# Mach1.net
KiCad netlist of a schematic drawn in Altium Designer
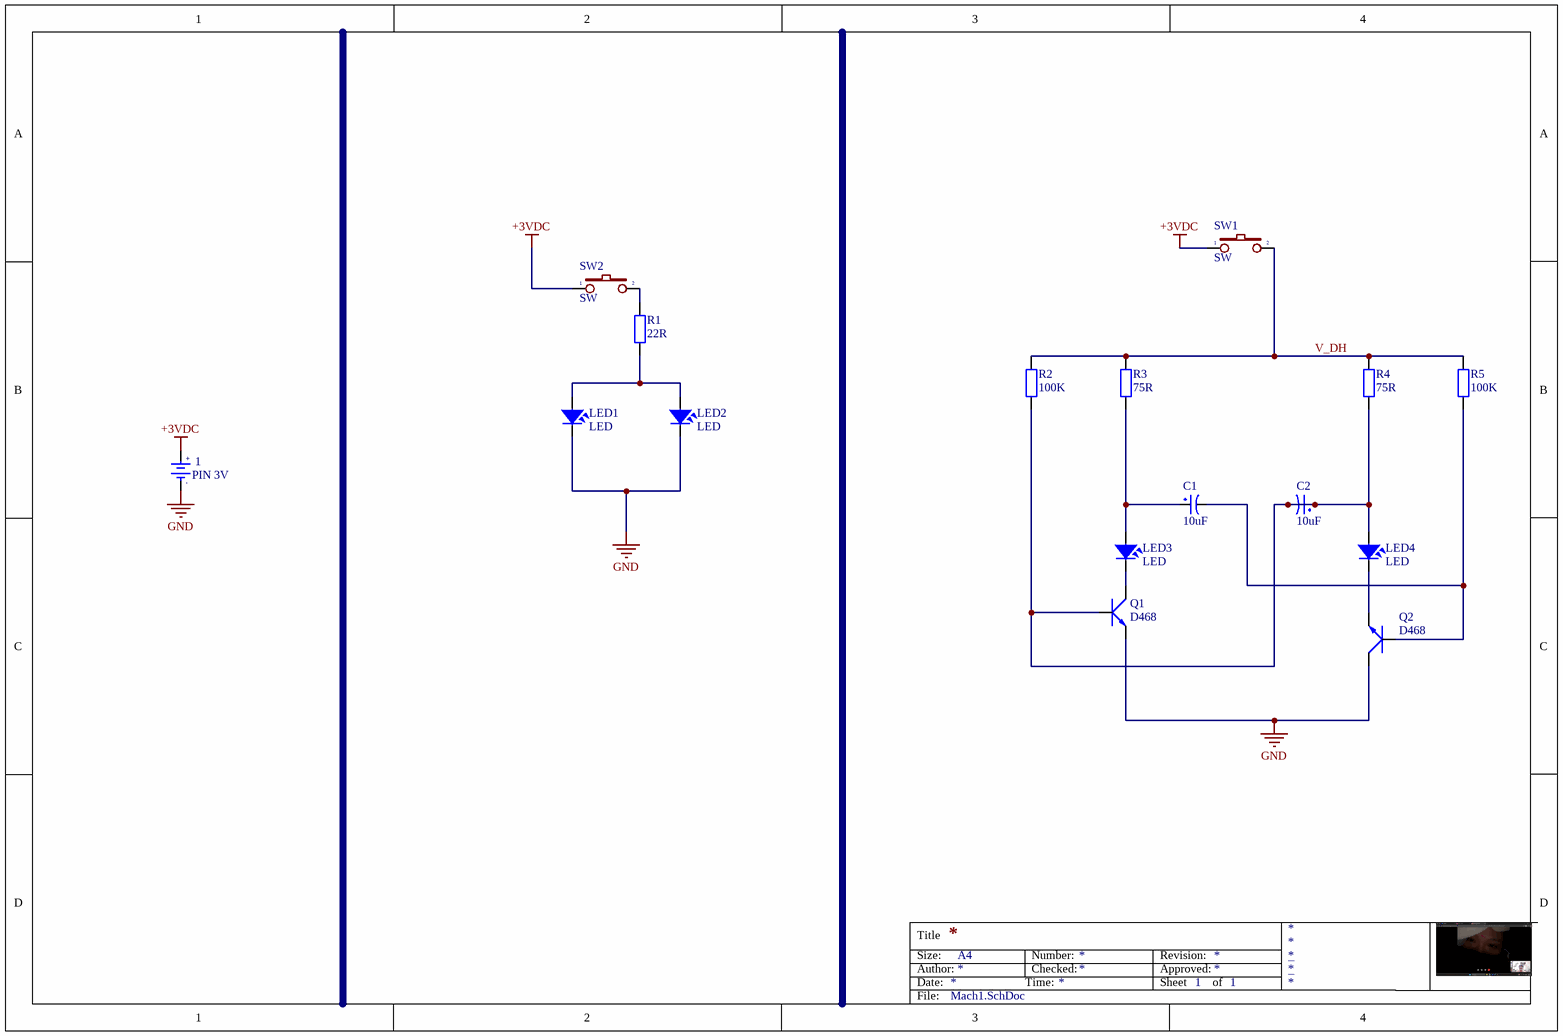
[diagram p0: Mach1.SchDoc]

(export (version "E")
  (design (tool "Eeschema 10.0.6"))
  (components
    (comp (ref "1")
      (value "PIN 3V")
      (footprint "PIN3V")
      (description "Battery 3VDC")
      (libsource (lib "KhanhBK_SCH_Library_2") (part "PIN 3V"))
    )
    (comp (ref "C1")
      (value "10uF")
      (footprint "CP1/2")
      (description "Cap P  0,1uF < 22uF , 16 - 50V")
      (libsource (lib "KhanhBK_SCH_Library_2") (part "CP1"))
    )
    (comp (ref "C2")
      (value "10uF")
      (footprint "CP1/2")
      (description "Cap P  0,1uF < 22uF , 16 - 50V")
      (libsource (lib "KhanhBK_SCH_Library_2") (part "CP1"))
    )
    (comp (ref "LED1")
      (value "LED")
      (footprint "LED-5 GRe")
      (description "LED Single colour Green and Red")
      (libsource (lib "KhanhBK_SCH_Library_2") (part "LED"))
    )
    (comp (ref "LED2")
      (value "LED")
      (footprint "LED-5 GRe")
      (description "LED Single colour Green and Red")
      (libsource (lib "KhanhBK_SCH_Library_2") (part "LED"))
    )
    (comp (ref "LED3")
      (value "LED")
      (footprint "LED-5 GRe")
      (description "LED Single colour Green and Red")
      (libsource (lib "KhanhBK_SCH_Library_2") (part "LED"))
    )
    (comp (ref "LED4")
      (value "LED")
      (footprint "LED-5TRED")
      (description "LED Single colour Green and Red")
      (libsource (lib "KhanhBK_SCH_Library_2") (part "LED"))
    )
    (comp (ref "Q1")
      (value "D468")
      (footprint "QTO-92")
      (description "P 600mW, ECB")
      (libsource (lib "KhanhBK_SCH_Library_2") (part "NPN_ECB"))
    )
    (comp (ref "Q2")
      (value "D468")
      (footprint "QTO-92")
      (description "P 600mW, ECB")
      (libsource (lib "KhanhBK_SCH_Library_2") (part "NPN_ECB"))
    )
    (comp (ref "R1")
      (value "22R")
      (footprint "RES-1/4W-SMALL")
      (description "Resistor 1/4W")
      (libsource (lib "KhanhBK_SCH_Library_2") (part "RES 1/4W"))
    )
    (comp (ref "R2")
      (value "100K")
      (footprint "RES-1/4W-SMALL")
      (description "Resistor 1/4W")
      (libsource (lib "KhanhBK_SCH_Library_2") (part "RES 1/4W"))
    )
    (comp (ref "R3")
      (value "75R")
      (footprint "RES-1/4W-SMALL")
      (description "Resistor 1/4W")
      (libsource (lib "KhanhBK_SCH_Library_2") (part "RES 1/4W"))
    )
    (comp (ref "R4")
      (value "75R")
      (footprint "RES-1/4W-SMALL")
      (description "Resistor 1/4W")
      (libsource (lib "KhanhBK_SCH_Library_2") (part "RES 1/4W"))
    )
    (comp (ref "R5")
      (value "100K")
      (footprint "RES-1/4W-SMALL")
      (description "Resistor 1/4W")
      (libsource (lib "KhanhBK_SCH_Library_2") (part "RES 1/4W"))
    )
    (comp (ref "SW1")
      (value "SW")
      (footprint "SW2")
      (description "Switch button 2 pin")
      (libsource (lib "KhanhBK_SCH_Library_2") (part "SW2"))
    )
    (comp (ref "SW2")
      (value "SW")
      (footprint "SW2")
      (description "Switch button 2 pin")
      (libsource (lib "KhanhBK_SCH_Library_2") (part "SW2"))
    )
  )
  (nets
    (net (code "1") (name "+3VDC") (class "Default")
      (node (ref "1") (pin "1") (pinfunction "+3V_1") (pintype "passive"))
      (node (ref "SW1") (pin "1") (pinfunction "1_1") (pintype "passive"))
      (node (ref "SW2") (pin "1") (pinfunction "1_1") (pintype "passive"))
    )
    (net (code "2") (name "/V_DH") (class "Default")
      (node (ref "R2") (pin "2") (pinfunction "2_2") (pintype "passive"))
      (node (ref "R3") (pin "2") (pinfunction "2_2") (pintype "passive"))
      (node (ref "R4") (pin "2") (pinfunction "2_2") (pintype "passive"))
      (node (ref "R5") (pin "2") (pinfunction "2_2") (pintype "passive"))
      (node (ref "SW1") (pin "2") (pinfunction "2_2") (pintype "passive"))
    )
    (net (code "3") (name "GND") (class "Default")
      (node (ref "1") (pin "2") (pinfunction "GND_2") (pintype "passive"))
      (node (ref "LED1") (pin "2") (pinfunction "2_2") (pintype "passive"))
      (node (ref "LED2") (pin "2") (pinfunction "2_2") (pintype "passive"))
      (node (ref "Q1") (pin "1") (pinfunction "E_1") (pintype "passive"))
      (node (ref "Q2") (pin "2") (pinfunction "C_2") (pintype "passive"))
    )
    (net (code "4") (name "Net-(C1-Pad1)") (class "Default")
      (node (ref "C1") (pin "1") (pinfunction "1_1") (pintype "passive"))
      (node (ref "LED3") (pin "1") (pinfunction "1_1") (pintype "passive"))
      (node (ref "R3") (pin "1") (pinfunction "1_1") (pintype "passive"))
    )
    (net (code "5") (name "Net-(LED1-Pad1)") (class "Default")
      (node (ref "LED1") (pin "1") (pinfunction "1_1") (pintype "passive"))
      (node (ref "LED2") (pin "1") (pinfunction "1_1") (pintype "passive"))
      (node (ref "R1") (pin "1") (pinfunction "1_1") (pintype "passive"))
    )
    (net (code "6") (name "Net-(Q1-B)") (class "Default")
      (node (ref "C2") (pin "1") (pinfunction "1_1") (pintype "passive"))
      (node (ref "C2") (pin "2") (pinfunction "2_2") (pintype "passive"))
      (node (ref "LED4") (pin "1") (pinfunction "1_1") (pintype "passive"))
      (node (ref "Q1") (pin "3") (pinfunction "B_3") (pintype "passive"))
      (node (ref "R2") (pin "1") (pinfunction "1_1") (pintype "passive"))
      (node (ref "R4") (pin "1") (pinfunction "1_1") (pintype "passive"))
    )
    (net (code "7") (name "Net-(Q1-C)") (class "Default")
      (node (ref "LED3") (pin "2") (pinfunction "2_2") (pintype "passive"))
      (node (ref "Q1") (pin "2") (pinfunction "C_2") (pintype "passive"))
    )
    (net (code "8") (name "Net-(Q2-B)") (class "Default")
      (node (ref "C1") (pin "2") (pinfunction "2_2") (pintype "passive"))
      (node (ref "Q2") (pin "3") (pinfunction "B_3") (pintype "passive"))
      (node (ref "R5") (pin "1") (pinfunction "1_1") (pintype "passive"))
    )
    (net (code "9") (name "Net-(Q2-E)") (class "Default")
      (node (ref "LED4") (pin "2") (pinfunction "2_2") (pintype "passive"))
      (node (ref "Q2") (pin "1") (pinfunction "E_1") (pintype "passive"))
    )
    (net (code "10") (name "Net-(R1-Pad2)") (class "Default")
      (node (ref "R1") (pin "2") (pinfunction "2_2") (pintype "passive"))
      (node (ref "SW2") (pin "2") (pinfunction "2_2") (pintype "passive"))
    )
  )
)
